# DRV8835_mini_drive_v6.net
KiCad netlist of a schematic drawn in EAGLE
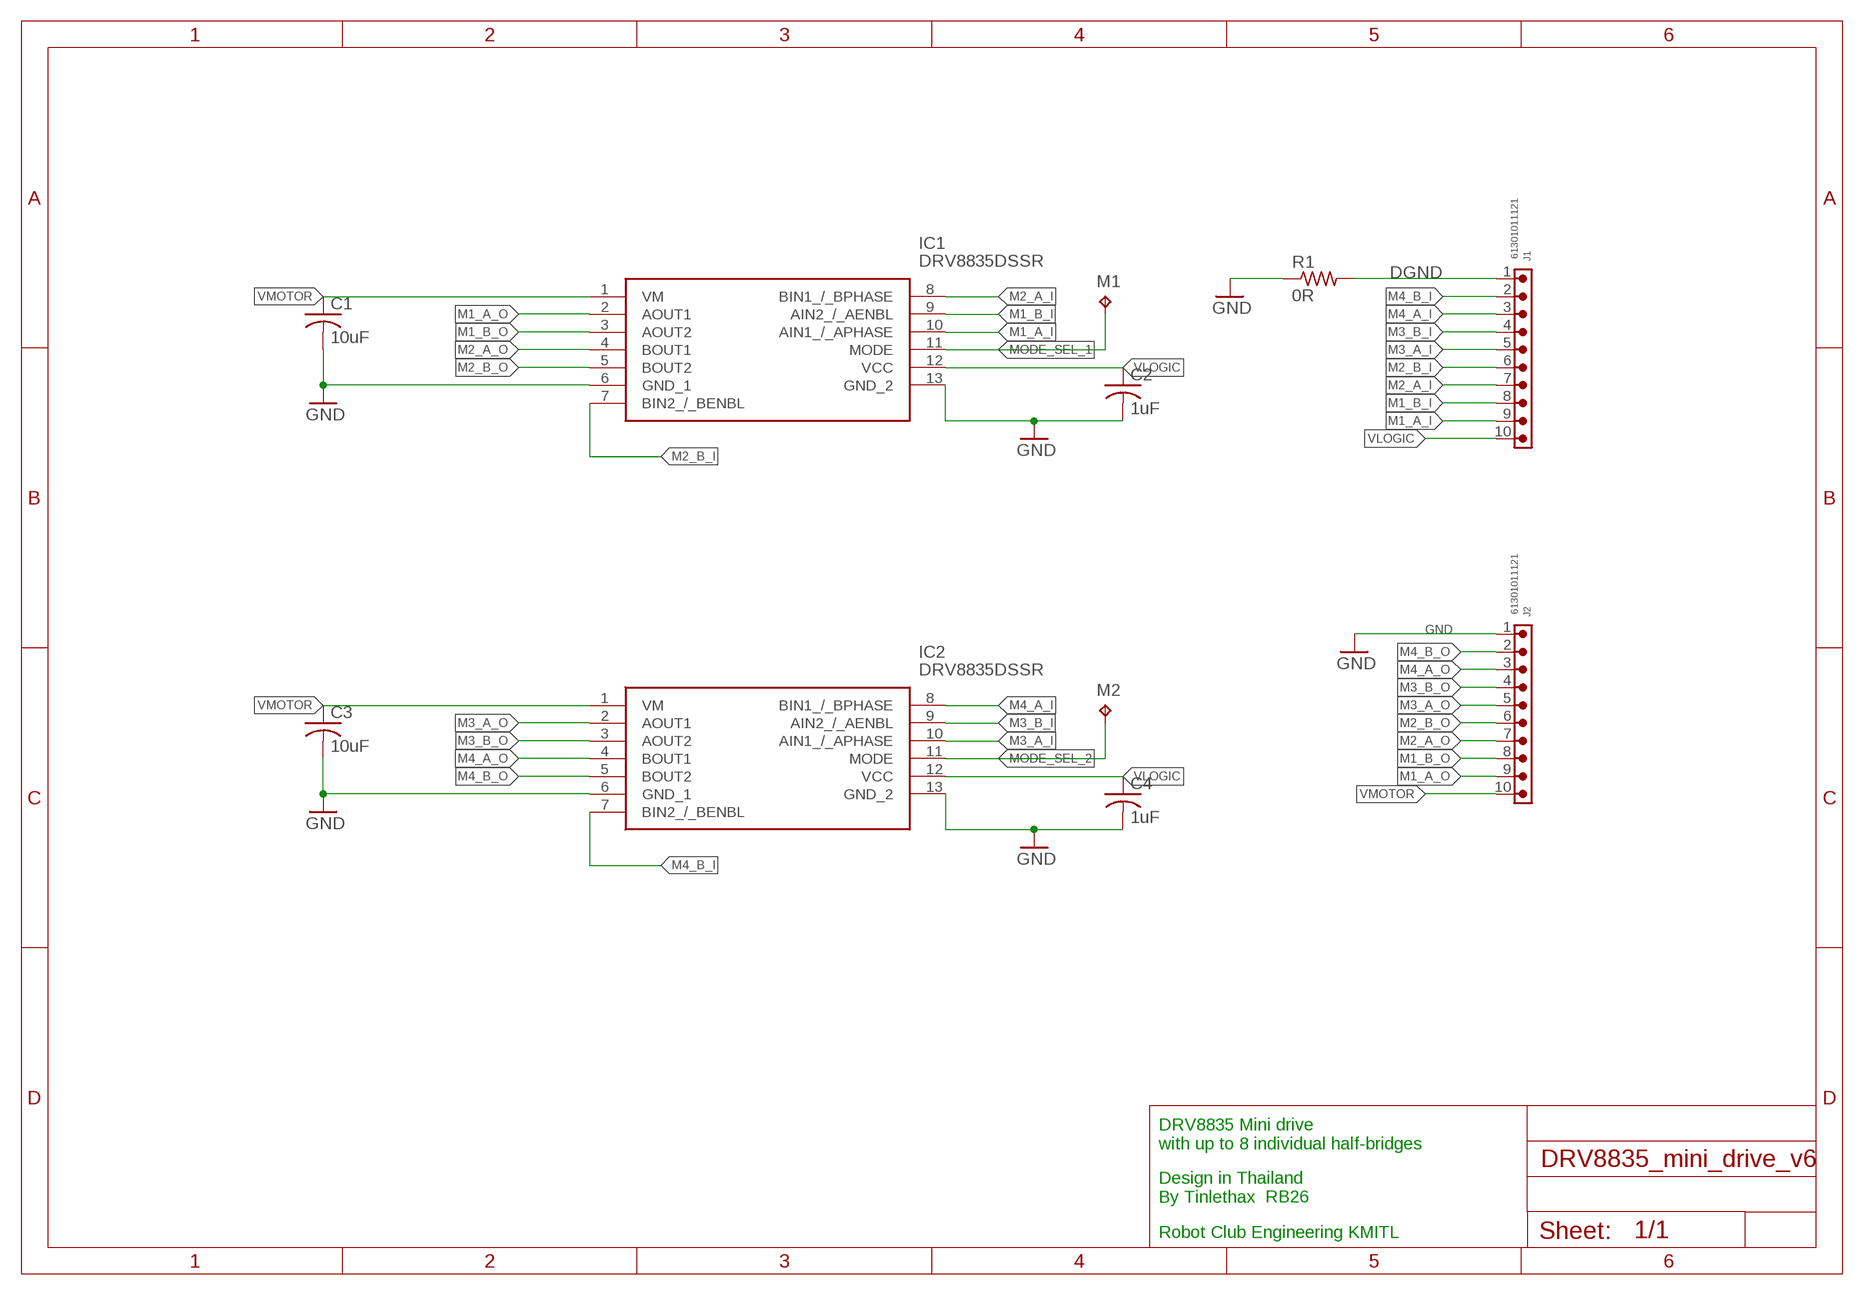
[diagram p0: schematic, sheet 1]

(export (version "E")
  (design (tool "Eeschema 10.0.6"))
  (components
    (comp (ref "C1")
      (value "10uF")
      (footprint "eagle-import:C0603")
      (libsource (lib "eagle-import") (part "C-USC0603"))
    )
    (comp (ref "C2")
      (value "1uF")
      (footprint "eagle-import:C0603")
      (libsource (lib "eagle-import") (part "C-USC0603"))
    )
    (comp (ref "C3")
      (value "10uF")
      (footprint "eagle-import:C0603")
      (libsource (lib "eagle-import") (part "C-USC0603"))
    )
    (comp (ref "C4")
      (value "1uF")
      (footprint "eagle-import:C0603")
      (libsource (lib "eagle-import") (part "C-USC0603"))
    )
    (comp (ref "IC1")
      (value "DRV8835DSSR")
      (footprint "eagle-import:DRV8835DSSR")
      (fields (field (name "MOUSER_PART_NUMBER") "595-DRV8835DSSR"))
      (libsource (lib "eagle-import") (part "DRV8835DSSR"))
    )
    (comp (ref "IC2")
      (value "DRV8835DSSR")
      (footprint "eagle-import:DRV8835DSSR")
      (fields (field (name "MOUSER_PART_NUMBER") "595-DRV8835DSSR"))
      (libsource (lib "eagle-import") (part "DRV8835DSSR"))
    )
    (comp (ref "J1")
      (value "61301011121")
      (footprint "eagle-import:61301011121")
      (libsource (lib "eagle-import") (part "6130XX11121_61301011121"))
    )
    (comp (ref "J2")
      (value "61301011121")
      (footprint "eagle-import:61301011121")
      (libsource (lib "eagle-import") (part "6130XX11121_61301011121"))
    )
    (comp (ref "M1")
      (value "TPTP10SQ")
      (footprint "eagle-import:TP10SQ")
      (libsource (lib "eagle-import") (part "TPTP10SQ"))
    )
    (comp (ref "M2")
      (value "TPTP10SQ")
      (footprint "eagle-import:TP10SQ")
      (libsource (lib "eagle-import") (part "TPTP10SQ"))
    )
    (comp (ref "R1")
      (value "0R")
      (footprint "eagle-import:R0805")
      (libsource (lib "eagle-import") (part "R-US_R0805"))
    )
  )
  (nets
    (net (code "1") (name "/DGND") (class "Default")
      (node (ref "J1") (pin "1") (pinfunction "1_1") (pintype "passive"))
      (node (ref "R1") (pin "2") (pinfunction "2_2") (pintype "passive"))
    )
    (net (code "2") (name "GND") (class "Default")
      (node (ref "C1") (pin "2") (pinfunction "2_2") (pintype "passive"))
      (node (ref "C2") (pin "2") (pinfunction "2_2") (pintype "passive"))
      (node (ref "C3") (pin "2") (pinfunction "2_2") (pintype "passive"))
      (node (ref "C4") (pin "2") (pinfunction "2_2") (pintype "passive"))
      (node (ref "IC1") (pin "13") (pinfunction "GND_2_13") (pintype "bidirectional"))
      (node (ref "IC1") (pin "6") (pinfunction "GND_1_6") (pintype "bidirectional"))
      (node (ref "IC2") (pin "13") (pinfunction "GND_2_13") (pintype "bidirectional"))
      (node (ref "IC2") (pin "6") (pinfunction "GND_1_6") (pintype "bidirectional"))
      (node (ref "J2") (pin "1") (pinfunction "1_1") (pintype "passive"))
      (node (ref "R1") (pin "1") (pinfunction "1_1") (pintype "passive"))
    )
    (net (code "3") (name "M1_A_I") (class "Default")
      (node (ref "IC1") (pin "10") (pinfunction "AIN1_/_APHASE_10") (pintype "bidirectional"))
      (node (ref "J1") (pin "9") (pinfunction "9_9") (pintype "passive"))
    )
    (net (code "4") (name "M1_A_O") (class "Default")
      (node (ref "IC1") (pin "2") (pinfunction "AOUT1_2") (pintype "bidirectional"))
      (node (ref "J2") (pin "9") (pinfunction "9_9") (pintype "passive"))
    )
    (net (code "5") (name "M1_B_I") (class "Default")
      (node (ref "IC1") (pin "9") (pinfunction "AIN2_/_AENBL_9") (pintype "bidirectional"))
      (node (ref "J1") (pin "8") (pinfunction "8_8") (pintype "passive"))
    )
    (net (code "6") (name "M1_B_O") (class "Default")
      (node (ref "IC1") (pin "3") (pinfunction "AOUT2_3") (pintype "bidirectional"))
      (node (ref "J2") (pin "8") (pinfunction "8_8") (pintype "passive"))
    )
    (net (code "7") (name "M2_A_I") (class "Default")
      (node (ref "IC1") (pin "8") (pinfunction "BIN1_/_BPHASE_8") (pintype "bidirectional"))
      (node (ref "J1") (pin "7") (pinfunction "7_7") (pintype "passive"))
    )
    (net (code "8") (name "M2_A_O") (class "Default")
      (node (ref "IC1") (pin "4") (pinfunction "BOUT1_4") (pintype "bidirectional"))
      (node (ref "J2") (pin "7") (pinfunction "7_7") (pintype "passive"))
    )
    (net (code "9") (name "M2_B_I") (class "Default")
      (node (ref "IC1") (pin "7") (pinfunction "BIN2_/_BENBL_7") (pintype "bidirectional"))
      (node (ref "J1") (pin "6") (pinfunction "6_6") (pintype "passive"))
    )
    (net (code "10") (name "M2_B_O") (class "Default")
      (node (ref "IC1") (pin "5") (pinfunction "BOUT2_5") (pintype "bidirectional"))
      (node (ref "J2") (pin "6") (pinfunction "6_6") (pintype "passive"))
    )
    (net (code "11") (name "M3_A_I") (class "Default")
      (node (ref "IC2") (pin "10") (pinfunction "AIN1_/_APHASE_10") (pintype "bidirectional"))
      (node (ref "J1") (pin "5") (pinfunction "5_5") (pintype "passive"))
    )
    (net (code "12") (name "M3_A_O") (class "Default")
      (node (ref "IC2") (pin "2") (pinfunction "AOUT1_2") (pintype "bidirectional"))
      (node (ref "J2") (pin "5") (pinfunction "5_5") (pintype "passive"))
    )
    (net (code "13") (name "M3_B_I") (class "Default")
      (node (ref "IC2") (pin "9") (pinfunction "AIN2_/_AENBL_9") (pintype "bidirectional"))
      (node (ref "J1") (pin "4") (pinfunction "4_4") (pintype "passive"))
    )
    (net (code "14") (name "M3_B_O") (class "Default")
      (node (ref "IC2") (pin "3") (pinfunction "AOUT2_3") (pintype "bidirectional"))
      (node (ref "J2") (pin "4") (pinfunction "4_4") (pintype "passive"))
    )
    (net (code "15") (name "M4_A_I") (class "Default")
      (node (ref "IC2") (pin "8") (pinfunction "BIN1_/_BPHASE_8") (pintype "bidirectional"))
      (node (ref "J1") (pin "3") (pinfunction "3_3") (pintype "passive"))
    )
    (net (code "16") (name "M4_A_O") (class "Default")
      (node (ref "IC2") (pin "4") (pinfunction "BOUT1_4") (pintype "bidirectional"))
      (node (ref "J2") (pin "3") (pinfunction "3_3") (pintype "passive"))
    )
    (net (code "17") (name "M4_B_I") (class "Default")
      (node (ref "IC2") (pin "7") (pinfunction "BIN2_/_BENBL_7") (pintype "bidirectional"))
      (node (ref "J1") (pin "2") (pinfunction "2_2") (pintype "passive"))
    )
    (net (code "18") (name "M4_B_O") (class "Default")
      (node (ref "IC2") (pin "5") (pinfunction "BOUT2_5") (pintype "bidirectional"))
      (node (ref "J2") (pin "2") (pinfunction "2_2") (pintype "passive"))
    )
    (net (code "19") (name "MODE_SEL_1") (class "Default")
      (node (ref "IC1") (pin "11") (pinfunction "MODE_11") (pintype "bidirectional"))
      (node (ref "M1") (pin "TP") (pinfunction "TP_TP") (pintype "input"))
    )
    (net (code "20") (name "MODE_SEL_2") (class "Default")
      (node (ref "IC2") (pin "11") (pinfunction "MODE_11") (pintype "bidirectional"))
      (node (ref "M2") (pin "TP") (pinfunction "TP_TP") (pintype "input"))
    )
    (net (code "21") (name "VLOGIC") (class "Default")
      (node (ref "C2") (pin "1") (pinfunction "1_1") (pintype "passive"))
      (node (ref "C4") (pin "1") (pinfunction "1_1") (pintype "passive"))
      (node (ref "IC1") (pin "12") (pinfunction "VCC_12") (pintype "bidirectional"))
      (node (ref "IC2") (pin "12") (pinfunction "VCC_12") (pintype "bidirectional"))
      (node (ref "J1") (pin "10") (pinfunction "10_10") (pintype "passive"))
    )
    (net (code "22") (name "VMOTOR") (class "Default")
      (node (ref "C1") (pin "1") (pinfunction "1_1") (pintype "passive"))
      (node (ref "C3") (pin "1") (pinfunction "1_1") (pintype "passive"))
      (node (ref "IC1") (pin "1") (pinfunction "VM_1") (pintype "bidirectional"))
      (node (ref "IC2") (pin "1") (pinfunction "VM_1") (pintype "bidirectional"))
      (node (ref "J2") (pin "10") (pinfunction "10_10") (pintype "passive"))
    )
  )
)
